# sch.net
KiCad netlist of a schematic drawn in EasyEDA
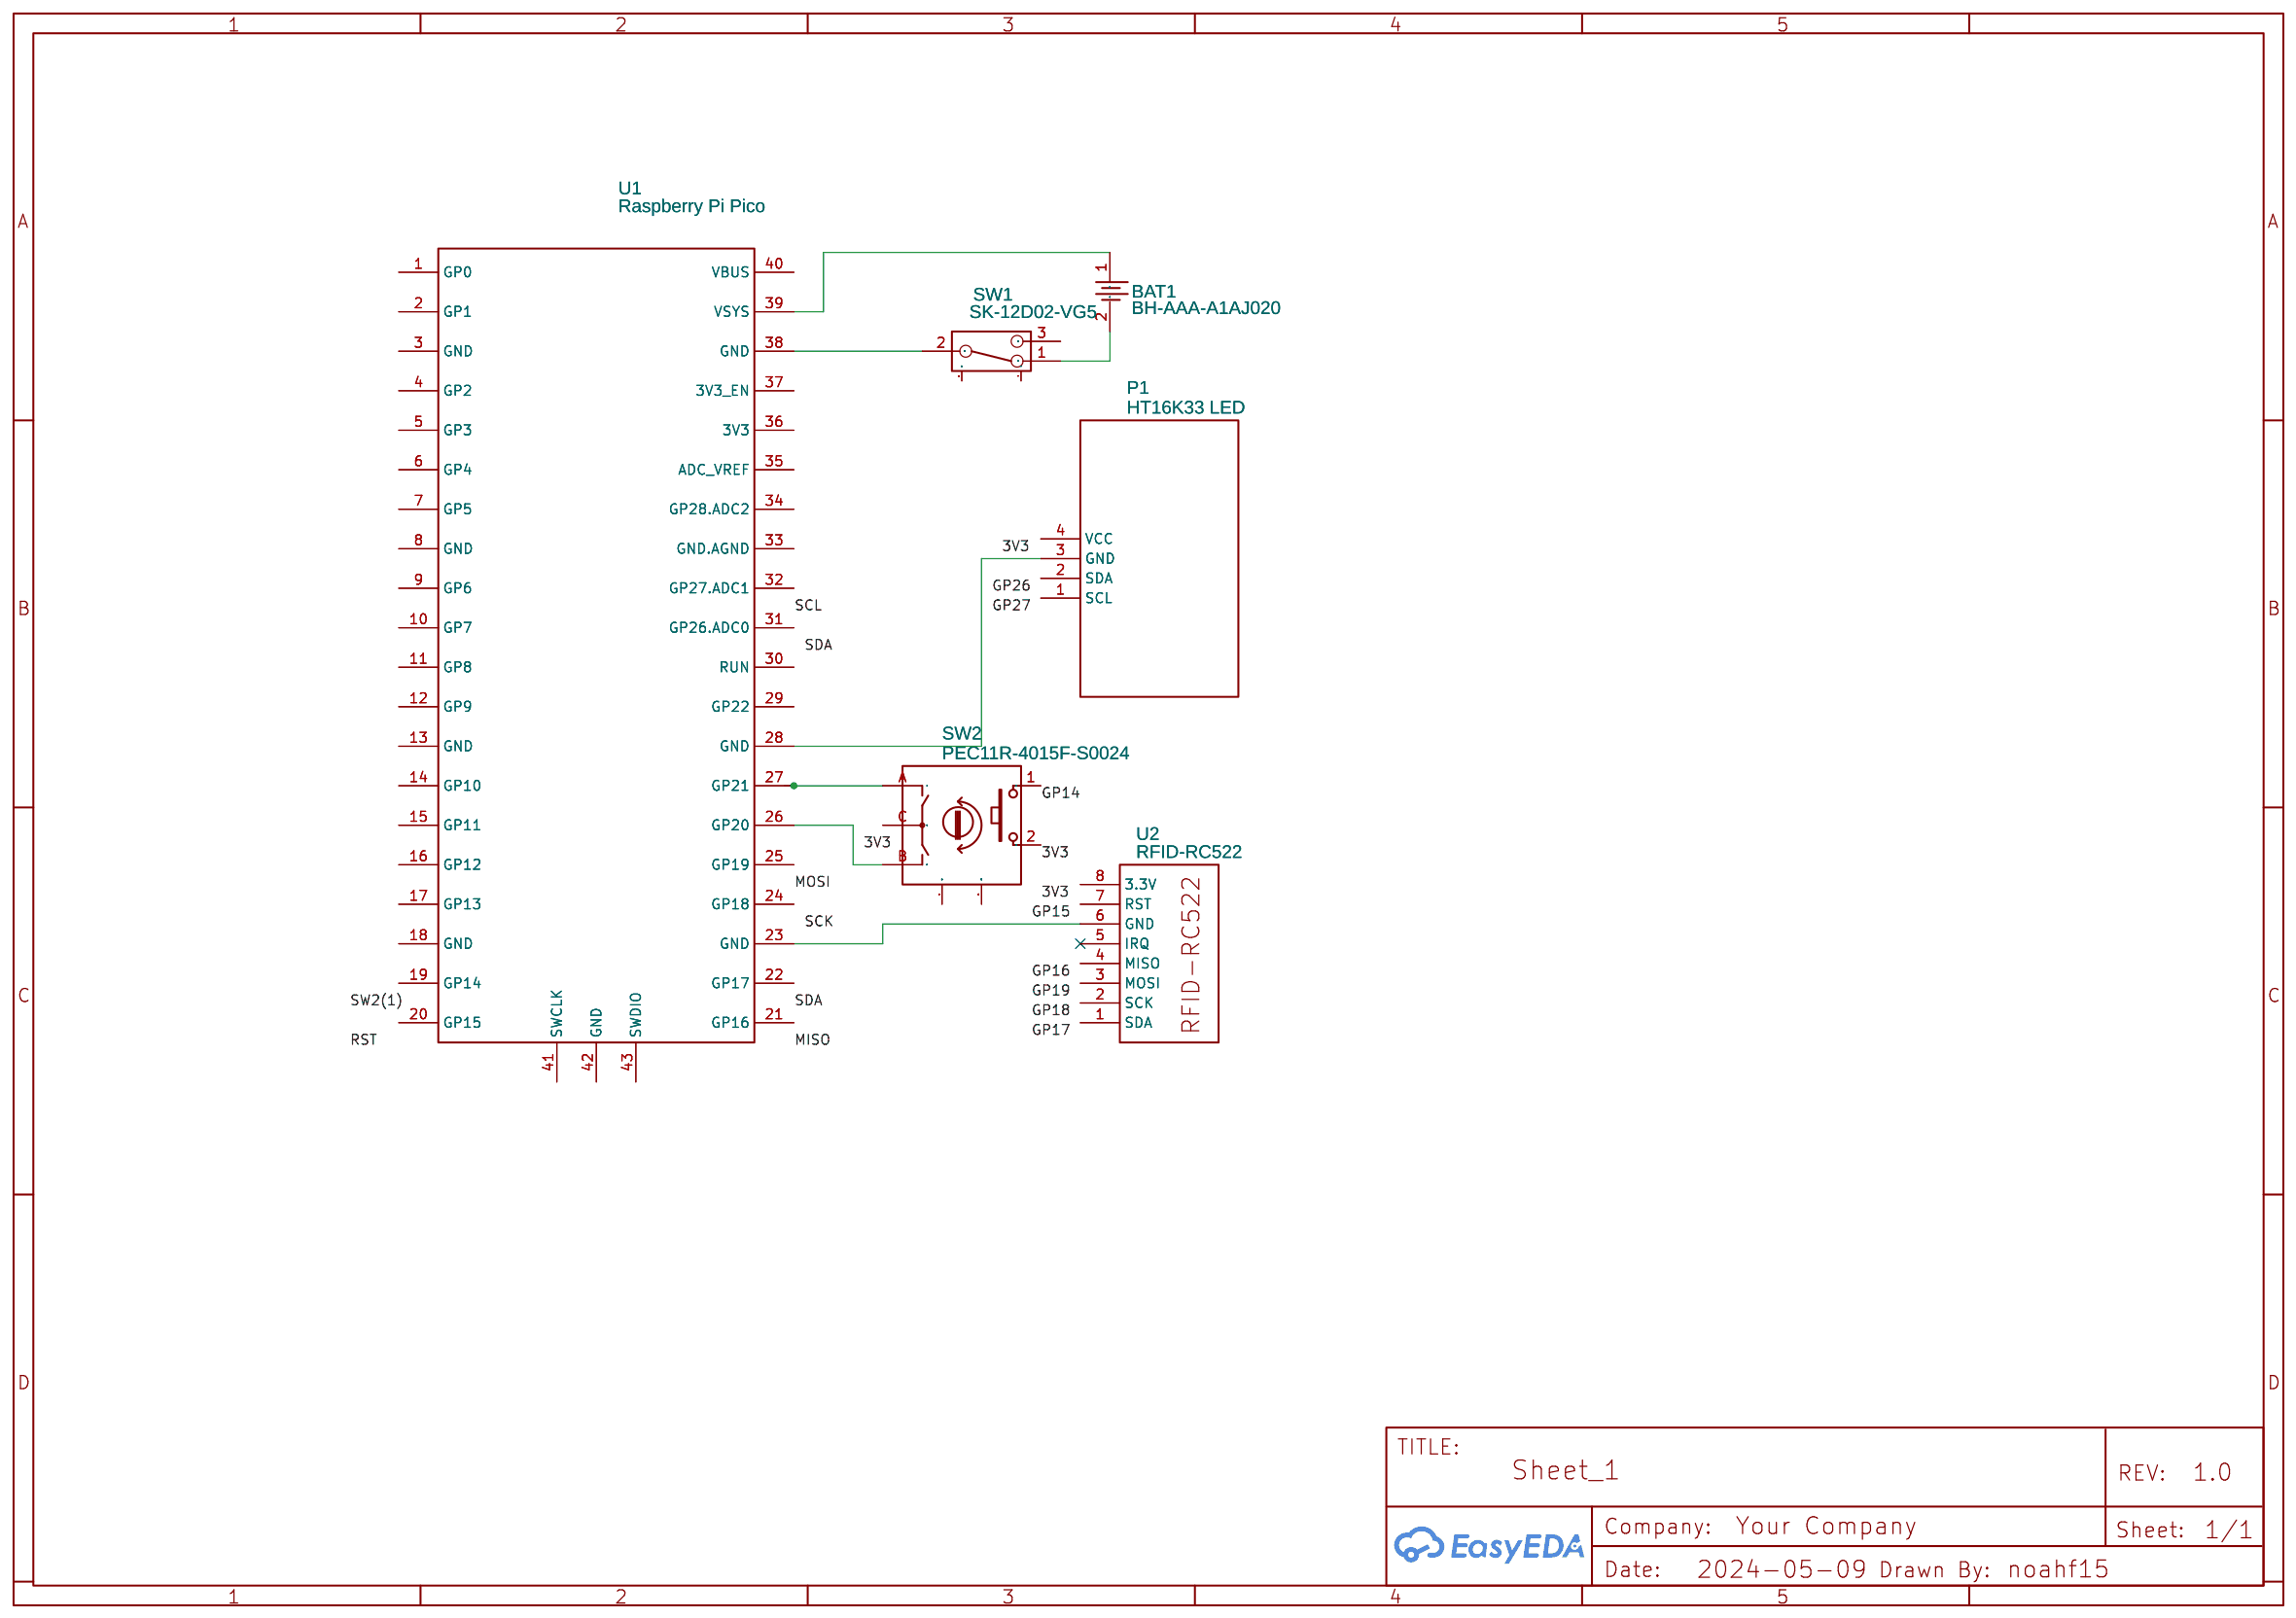
[diagram p0: schematic sheet]

(export (version "E")
  (design (tool "Eeschema 10.0.6"))
  (components
    (comp (ref "BAT1")
      (value "BH-AAA-A1AJ020")
      (fields (field (name "Manufacturer") "MYOUNG(美阳)"))
      (libsource (lib "") (part "BH-AAA-A1AJ020"))
    )
    (comp (ref "P1") (value "HT16K33 LED") (libsource (lib "") (part "HT16K33 LED")))
    (comp (ref "SW1")
      (value "SK-12D02-VG5")
      (fields (field (name "Manufacturer") "Rectangular Connectors - Contacts"))
      (libsource (lib "") (part "SK-12D02-VG5"))
    )
    (comp (ref "SW2")
      (value "PEC11R-4015F-S0024")
      (fields (field (name "Manufacturer") "BOURNS"))
      (libsource (lib "") (part "PEC11R-4015F-S0024"))
    )
    (comp (ref "U1")
      (value "Raspberry Pi Pico")
      (fields (field (name "Manufacturer") "Raspberry Pi Foundation"))
      (libsource (lib "") (part "Raspberry Pi Pico"))
    )
    (comp (ref "U2") (value "RFID-RC522") (libsource (lib "") (part "RFID-RC522")))
  )
  (nets
    (net (code "17") (name "Net-(BAT1-Pad2)") (class "Default")
      (node (ref "BAT1") (pin "2") (pinfunction "2_2") (pintype "input"))
      (node (ref "SW1") (pin "1") (pinfunction "1_1") (pintype "unspecified"))
    )
    (net (code "18") (name "Net-(P1-GND)") (class "Default")
      (node (ref "P1") (pin "3") (pinfunction "GND_3") (pintype "unspecified"))
      (node (ref "U1") (pin "28") (pinfunction "GND_28") (pintype "passive"))
    )
    (net (code "19") (name "Net-(SW1-Pad2)") (class "Default")
      (node (ref "SW1") (pin "2") (pinfunction "2_2") (pintype "unspecified"))
      (node (ref "U1") (pin "38") (pinfunction "GND_38") (pintype "passive"))
    )
    (net (code "20") (name "Net-(U1-GP20)") (class "Default")
      (node (ref "SW2") (pin "B") (pinfunction "B_B") (pintype "unspecified"))
      (node (ref "U1") (pin "26") (pinfunction "GP20_26") (pintype "bidirectional"))
    )
    (net (code "21") (name "Net-(U1-GP21)") (class "Default")
      (node (ref "SW2") (pin "A") (pinfunction "A_A") (pintype "unspecified"))
      (node (ref "U1") (pin "27") (pinfunction "GP21_27") (pintype "bidirectional"))
    )
    (net (code "22") (name "Net-(U1-VSYS)") (class "Default")
      (node (ref "BAT1") (pin "1") (pinfunction "1_1") (pintype "input"))
      (node (ref "U1") (pin "39") (pinfunction "VSYS_39") (pintype "passive"))
    )
    (net (code "23") (name "Net-(U2-GND)") (class "Default")
      (node (ref "U1") (pin "23") (pinfunction "GND_23") (pintype "passive"))
      (node (ref "U2") (pin "6") (pinfunction "GND_6") (pintype "unspecified"))
    )
    (net (code "24") (name "unconnected-(P1-SCL-Pad1)") (class "Default")
      (node (ref "P1") (pin "1") (pinfunction "SCL_1") (pintype "unspecified"))
    )
    (net (code "25") (name "unconnected-(P1-SDA-Pad2)") (class "Default")
      (node (ref "P1") (pin "2") (pinfunction "SDA_2") (pintype "unspecified"))
    )
    (net (code "26") (name "unconnected-(P1-VCC-Pad4)") (class "Default")
      (node (ref "P1") (pin "4") (pinfunction "VCC_4") (pintype "unspecified"))
    )
    (net (code "27") (name "unconnected-(SW1-Pad3)") (class "Default")
      (node (ref "SW1") (pin "3") (pinfunction "3_3") (pintype "unspecified"))
    )
    (net (code "28") (name "unconnected-(SW1-Pad4)") (class "Default")
      (node (ref "SW1") (pin "4") (pinfunction "4_4") (pintype "unspecified"))
    )
    (net (code "29") (name "unconnected-(SW1-Pad5)") (class "Default")
      (node (ref "SW1") (pin "5") (pinfunction "5_5") (pintype "unspecified"))
    )
    (net (code "30") (name "unconnected-(SW2-Pad1)") (class "Default")
      (node (ref "SW2") (pin "1") (pinfunction "1_1") (pintype "unspecified"))
    )
    (net (code "31") (name "unconnected-(SW2-Pad2)") (class "Default")
      (node (ref "SW2") (pin "2") (pinfunction "2_2") (pintype "unspecified"))
    )
    (net (code "32") (name "unconnected-(SW2-PadC)") (class "Default")
      (node (ref "SW2") (pin "C") (pinfunction "C_C") (pintype "unspecified"))
    )
    (net (code "33") (name "unconnected-(SW2-PadMT1)") (class "Default")
      (node (ref "SW2") (pin "MT1") (pinfunction "MT1_MT1") (pintype "unspecified"))
    )
    (net (code "34") (name "unconnected-(SW2-PadMT2)") (class "Default")
      (node (ref "SW2") (pin "MT2") (pinfunction "MT2_MT2") (pintype "unspecified"))
    )
    (net (code "35") (name "unconnected-(U1-3V3-Pad36)") (class "Default")
      (node (ref "U1") (pin "36") (pinfunction "3V3_36") (pintype "passive"))
    )
    (net (code "36") (name "unconnected-(U1-3V3_EN-Pad37)") (class "Default")
      (node (ref "U1") (pin "37") (pinfunction "3V3_EN_37") (pintype "input"))
    )
    (net (code "37") (name "unconnected-(U1-ADC_VREF-Pad35)") (class "Default")
      (node (ref "U1") (pin "35") (pinfunction "ADC_VREF_35") (pintype "passive"))
    )
    (net (code "38") (name "unconnected-(U1-GND-Pad3)") (class "Default")
      (node (ref "U1") (pin "3") (pinfunction "GND_3") (pintype "passive"))
    )
    (net (code "39") (name "unconnected-(U1-GND-Pad8)") (class "Default")
      (node (ref "U1") (pin "8") (pinfunction "GND_8") (pintype "passive"))
    )
    (net (code "40") (name "unconnected-(U1-GND-Pad13)") (class "Default")
      (node (ref "U1") (pin "13") (pinfunction "GND_13") (pintype "passive"))
    )
    (net (code "41") (name "unconnected-(U1-GND-Pad18)") (class "Default")
      (node (ref "U1") (pin "18") (pinfunction "GND_18") (pintype "passive"))
    )
    (net (code "42") (name "unconnected-(U1-GND-Pad42)") (class "Default")
      (node (ref "U1") (pin "42") (pinfunction "GND_42") (pintype "passive"))
    )
    (net (code "43") (name "unconnected-(U1-GND.AGND-Pad33)") (class "Default")
      (node (ref "U1") (pin "33") (pinfunction "GND.AGND_33") (pintype "passive"))
    )
    (net (code "44") (name "unconnected-(U1-GP0-Pad1)") (class "Default")
      (node (ref "U1") (pin "1") (pinfunction "GP0_1") (pintype "bidirectional"))
    )
    (net (code "45") (name "unconnected-(U1-GP1-Pad2)") (class "Default")
      (node (ref "U1") (pin "2") (pinfunction "GP1_2") (pintype "bidirectional"))
    )
    (net (code "46") (name "unconnected-(U1-GP2-Pad4)") (class "Default")
      (node (ref "U1") (pin "4") (pinfunction "GP2_4") (pintype "bidirectional"))
    )
    (net (code "47") (name "unconnected-(U1-GP3-Pad5)") (class "Default")
      (node (ref "U1") (pin "5") (pinfunction "GP3_5") (pintype "bidirectional"))
    )
    (net (code "48") (name "unconnected-(U1-GP4-Pad6)") (class "Default")
      (node (ref "U1") (pin "6") (pinfunction "GP4_6") (pintype "bidirectional"))
    )
    (net (code "49") (name "unconnected-(U1-GP5-Pad7)") (class "Default")
      (node (ref "U1") (pin "7") (pinfunction "GP5_7") (pintype "bidirectional"))
    )
    (net (code "50") (name "unconnected-(U1-GP6-Pad9)") (class "Default")
      (node (ref "U1") (pin "9") (pinfunction "GP6_9") (pintype "bidirectional"))
    )
    (net (code "51") (name "unconnected-(U1-GP7-Pad10)") (class "Default")
      (node (ref "U1") (pin "10") (pinfunction "GP7_10") (pintype "bidirectional"))
    )
    (net (code "52") (name "unconnected-(U1-GP8-Pad11)") (class "Default")
      (node (ref "U1") (pin "11") (pinfunction "GP8_11") (pintype "bidirectional"))
    )
    (net (code "53") (name "unconnected-(U1-GP9-Pad12)") (class "Default")
      (node (ref "U1") (pin "12") (pinfunction "GP9_12") (pintype "bidirectional"))
    )
    (net (code "54") (name "unconnected-(U1-GP10-Pad14)") (class "Default")
      (node (ref "U1") (pin "14") (pinfunction "GP10_14") (pintype "bidirectional"))
    )
    (net (code "55") (name "unconnected-(U1-GP11-Pad15)") (class "Default")
      (node (ref "U1") (pin "15") (pinfunction "GP11_15") (pintype "bidirectional"))
    )
    (net (code "56") (name "unconnected-(U1-GP12-Pad16)") (class "Default")
      (node (ref "U1") (pin "16") (pinfunction "GP12_16") (pintype "bidirectional"))
    )
    (net (code "57") (name "unconnected-(U1-GP13-Pad17)") (class "Default")
      (node (ref "U1") (pin "17") (pinfunction "GP13_17") (pintype "bidirectional"))
    )
    (net (code "58") (name "unconnected-(U1-GP14-Pad19)") (class "Default")
      (node (ref "U1") (pin "19") (pinfunction "GP14_19") (pintype "bidirectional"))
    )
    (net (code "59") (name "unconnected-(U1-GP15-Pad20)") (class "Default")
      (node (ref "U1") (pin "20") (pinfunction "GP15_20") (pintype "bidirectional"))
    )
    (net (code "60") (name "unconnected-(U1-GP16-Pad21)") (class "Default")
      (node (ref "U1") (pin "21") (pinfunction "GP16_21") (pintype "bidirectional"))
    )
    (net (code "61") (name "unconnected-(U1-GP17-Pad22)") (class "Default")
      (node (ref "U1") (pin "22") (pinfunction "GP17_22") (pintype "bidirectional"))
    )
    (net (code "62") (name "unconnected-(U1-GP18-Pad24)") (class "Default")
      (node (ref "U1") (pin "24") (pinfunction "GP18_24") (pintype "bidirectional"))
    )
    (net (code "63") (name "unconnected-(U1-GP19-Pad25)") (class "Default")
      (node (ref "U1") (pin "25") (pinfunction "GP19_25") (pintype "bidirectional"))
    )
    (net (code "64") (name "unconnected-(U1-GP22-Pad29)") (class "Default")
      (node (ref "U1") (pin "29") (pinfunction "GP22_29") (pintype "bidirectional"))
    )
    (net (code "65") (name "unconnected-(U1-GP26.ADC0-Pad31)") (class "Default")
      (node (ref "U1") (pin "31") (pinfunction "GP26.ADC0_31") (pintype "bidirectional"))
    )
    (net (code "66") (name "unconnected-(U1-GP27.ADC1-Pad32)") (class "Default")
      (node (ref "U1") (pin "32") (pinfunction "GP27.ADC1_32") (pintype "bidirectional"))
    )
    (net (code "67") (name "unconnected-(U1-GP28.ADC2-Pad34)") (class "Default")
      (node (ref "U1") (pin "34") (pinfunction "GP28.ADC2_34") (pintype "bidirectional"))
    )
    (net (code "68") (name "unconnected-(U1-RUN-Pad30)") (class "Default")
      (node (ref "U1") (pin "30") (pinfunction "RUN_30") (pintype "unspecified"))
    )
    (net (code "69") (name "unconnected-(U1-SWCLK-Pad41)") (class "Default")
      (node (ref "U1") (pin "41") (pinfunction "SWCLK_41") (pintype "bidirectional"))
    )
    (net (code "70") (name "unconnected-(U1-SWDIO-Pad43)") (class "Default")
      (node (ref "U1") (pin "43") (pinfunction "SWDIO_43") (pintype "bidirectional"))
    )
    (net (code "71") (name "unconnected-(U1-VBUS-Pad40)") (class "Default")
      (node (ref "U1") (pin "40") (pinfunction "VBUS_40") (pintype "passive"))
    )
    (net (code "72") (name "unconnected-(U2-3.3V-Pad8)") (class "Default")
      (node (ref "U2") (pin "8") (pinfunction "3.3V_8") (pintype "unspecified"))
    )
    (net (code "73") (name "unconnected-(U2-IRQ-Pad5)") (class "Default")
      (node (ref "U2") (pin "5") (pinfunction "IRQ_5") (pintype "unspecified+no_connect"))
    )
    (net (code "74") (name "unconnected-(U2-MISO-Pad4)") (class "Default")
      (node (ref "U2") (pin "4") (pinfunction "MISO_4") (pintype "unspecified"))
    )
    (net (code "75") (name "unconnected-(U2-MOSI-Pad3)") (class "Default")
      (node (ref "U2") (pin "3") (pinfunction "MOSI_3") (pintype "unspecified"))
    )
    (net (code "76") (name "unconnected-(U2-RST-Pad7)") (class "Default")
      (node (ref "U2") (pin "7") (pinfunction "RST_7") (pintype "unspecified"))
    )
    (net (code "77") (name "unconnected-(U2-SCK-Pad2)") (class "Default")
      (node (ref "U2") (pin "2") (pinfunction "SCK_2") (pintype "unspecified"))
    )
    (net (code "78") (name "unconnected-(U2-SDA-Pad1)") (class "Default")
      (node (ref "U2") (pin "1") (pinfunction "SDA_1") (pintype "unspecified"))
    )
  )
)
